# PROC054D_AWR_Pull_Resistors.net
KiCad netlist of a schematic drawn in Altium Designer
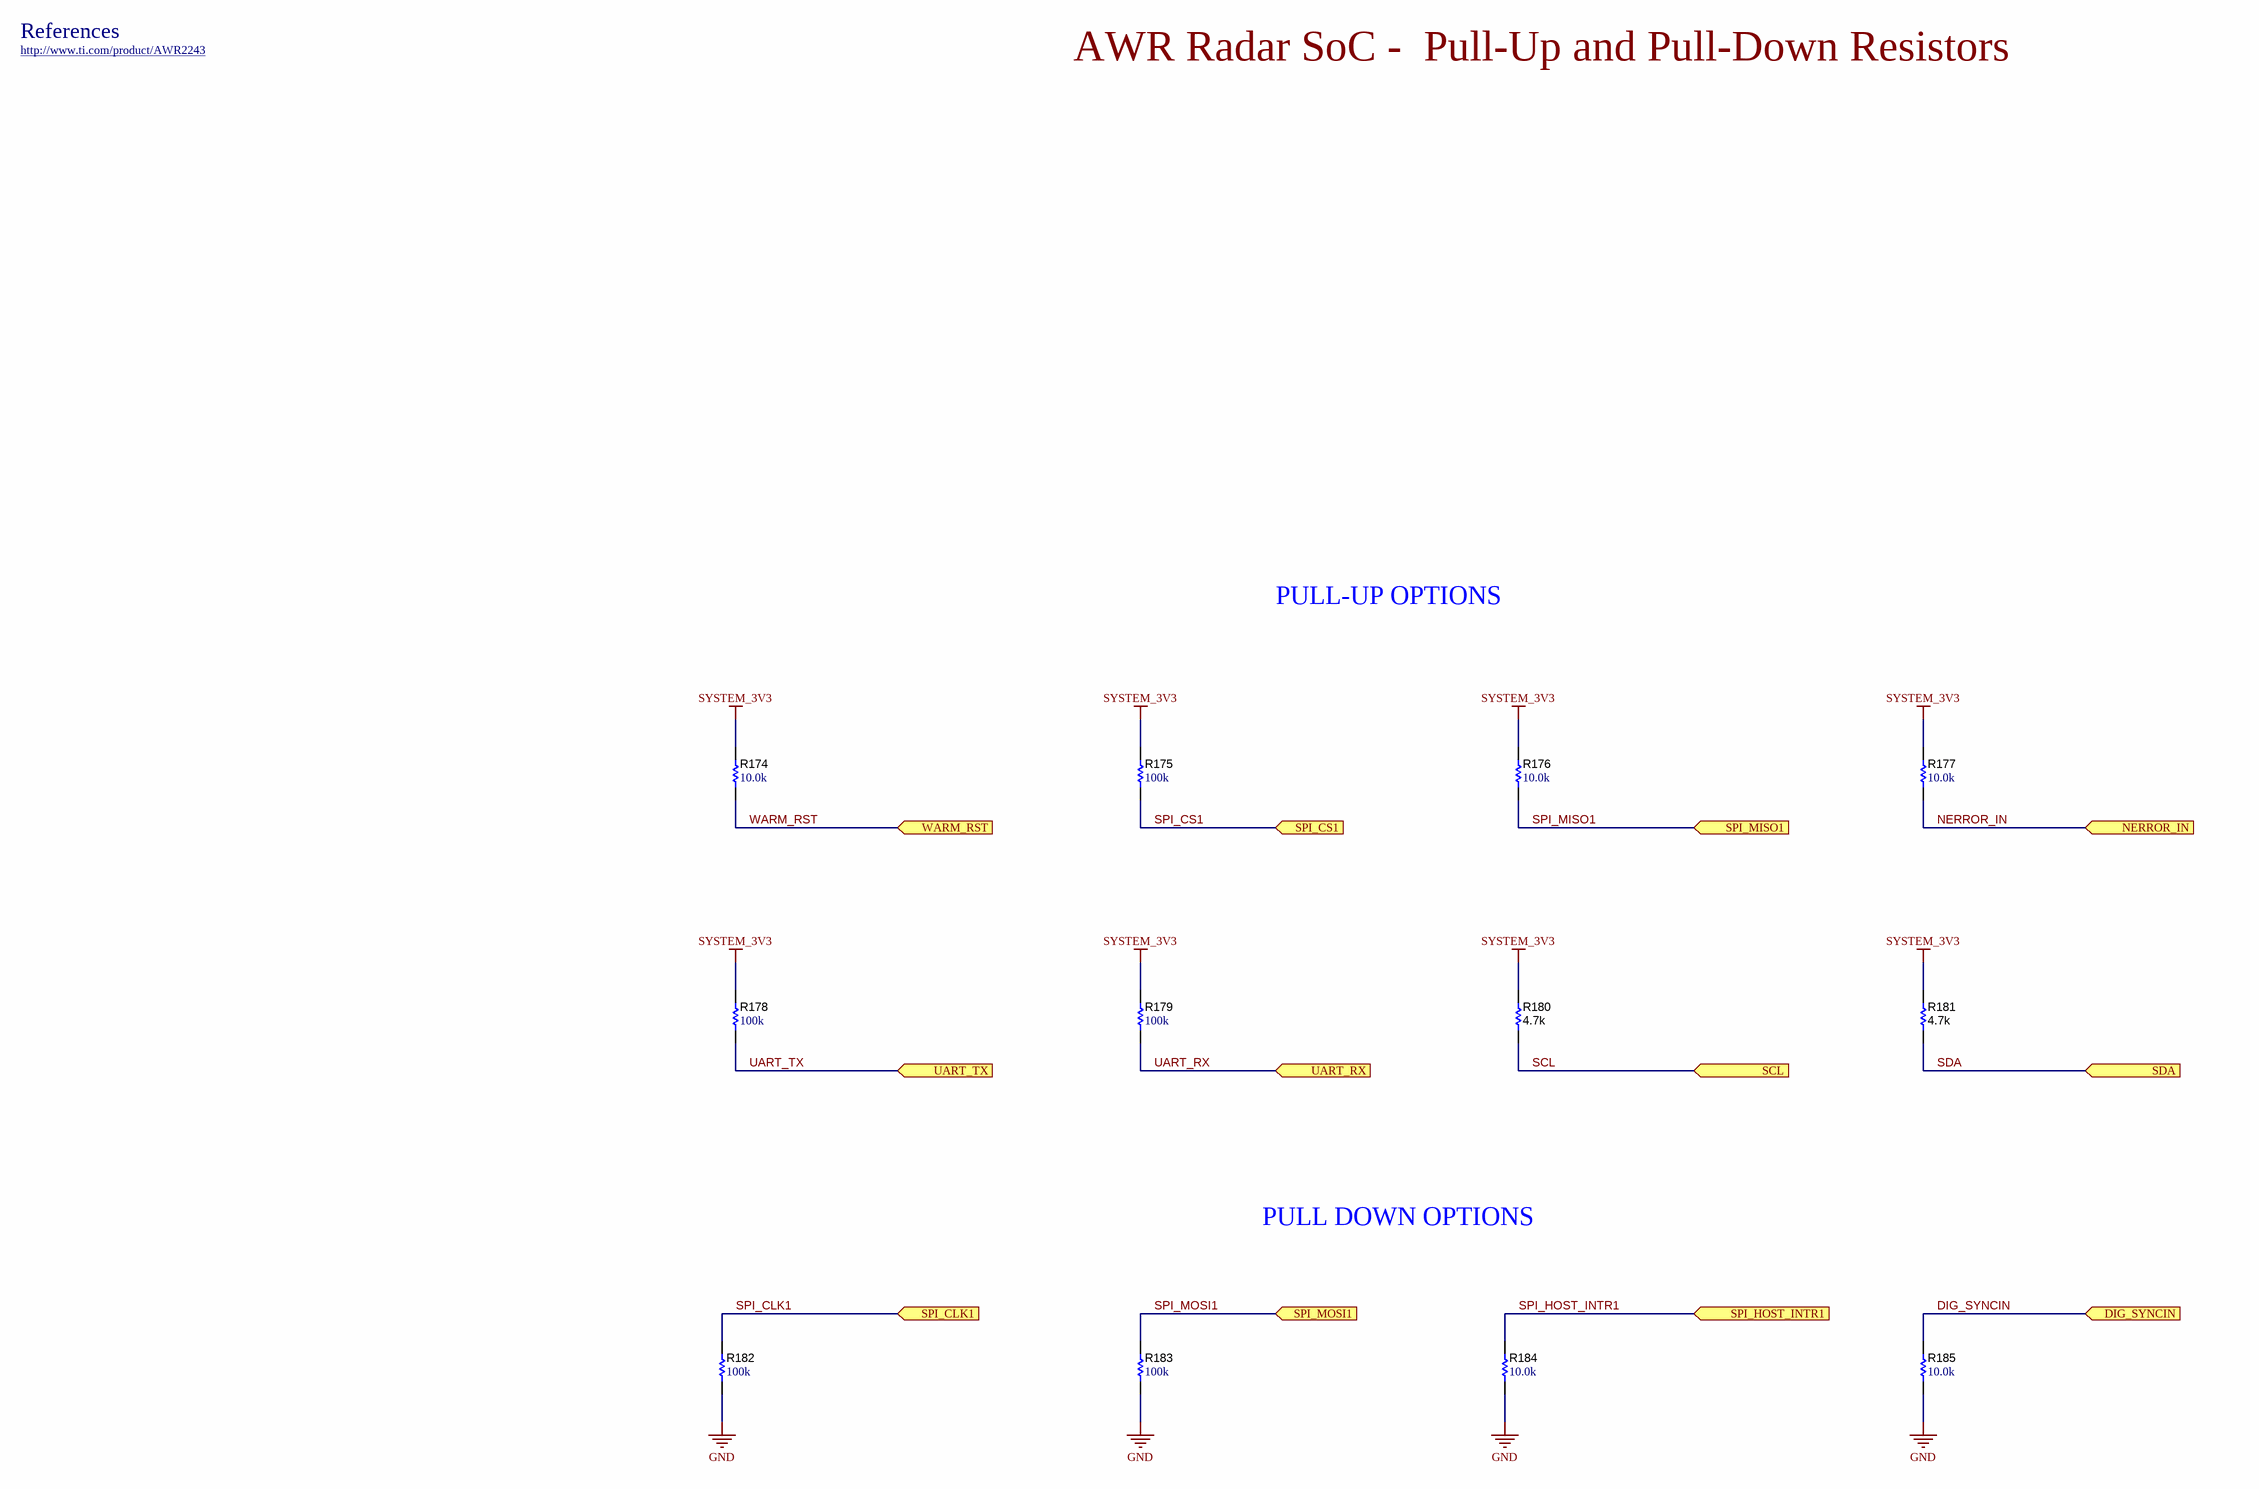
[diagram p0: PROC054D_AWR_Pull_Resistors.SchDoc]

(export (version "E")
  (design (tool "Eeschema 10.0.6"))
  (components
    (comp (ref "R174")
      (value "CRCW040210K0FKED")
      (footprint "0402")
      (description "RES, 10.0 k, 1%, 0.063 W, AEC-Q200 Grade 0, 0402")
      (fields (field (name "MANUFACTURER") "Vishay-Dale") (field (name "VALUEDISPLAYED") "10.0k"))
      (libsource (lib "Altium Vault - TI") (part "Resistor"))
    )
    (comp (ref "R175")
      (value "CRCW0402100KFKED")
      (footprint "0402")
      (description "RES, 100 k, 1%, 0.063 W, AEC-Q200 Grade 0, 0402")
      (fields (field (name "MANUFACTURER") "Vishay-Dale") (field (name "VALUEDISPLAYED") "100k"))
      (libsource (lib "Altium Vault - TI") (part "Resistor"))
    )
    (comp (ref "R176")
      (value "CRCW040210K0FKED")
      (footprint "0402")
      (description "RES, 10.0 k, 1%, 0.063 W, AEC-Q200 Grade 0, 0402")
      (fields (field (name "MANUFACTURER") "Vishay-Dale") (field (name "VALUEDISPLAYED") "10.0k"))
      (libsource (lib "Altium Vault - TI") (part "Resistor"))
    )
    (comp (ref "R177")
      (value "CRCW040210K0FKED")
      (footprint "0402S")
      (description "RES, 10.0 k, 1%, 0.063 W, AEC-Q200 Grade 0, 0402")
      (fields (field (name "MANUFACTURER") "Vishay-Dale") (field (name "VALUEDISPLAYED") "10.0k"))
      (libsource (lib "Altium Vault - TI") (part "Resistor"))
    )
    (comp (ref "R178")
      (value "CRCW0402100KFKED")
      (footprint "0402")
      (description "RES, 100 k, 1%, 0.063 W, AEC-Q200 Grade 0, 0402")
      (fields (field (name "MANUFACTURER") "Vishay-Dale") (field (name "VALUEDISPLAYED") "100k"))
      (libsource (lib "Altium Vault - TI") (part "Resistor"))
    )
    (comp (ref "R179")
      (value "CRCW0402100KFKED")
      (footprint "0402")
      (description "RES, 100 k, 1%, 0.063 W, AEC-Q200 Grade 0, 0402")
      (fields (field (name "MANUFACTURER") "Vishay-Dale") (field (name "VALUEDISPLAYED") "100k"))
      (libsource (lib "Altium Vault - TI") (part "Resistor"))
    )
    (comp (ref "R180")
      (value "CRCW04024K70JNED")
      (footprint "0402S")
      (description "RES, 4.7 k, 5%, 0.063 W, AEC-Q200 Grade 0, 0402")
      (fields (field (name "MANUFACTURER") "Vishay-Dale") (field (name "VALUEDISPLAYED") "4.7k"))
      (libsource (lib "Altium Vault - TI") (part "Resistor"))
    )
    (comp (ref "R181")
      (value "CRCW04024K70JNED")
      (footprint "0402S")
      (description "RES, 4.7 k, 5%, 0.063 W, AEC-Q200 Grade 0, 0402")
      (fields (field (name "MANUFACTURER") "Vishay-Dale") (field (name "VALUEDISPLAYED") "4.7k"))
      (libsource (lib "Altium Vault - TI") (part "Resistor"))
    )
    (comp (ref "R182")
      (value "CRCW0402100KFKED")
      (footprint "0402")
      (description "RES, 100 k, 1%, 0.063 W, AEC-Q200 Grade 0, 0402")
      (fields (field (name "MANUFACTURER") "Vishay-Dale") (field (name "VALUEDISPLAYED") "100k"))
      (libsource (lib "Altium Vault - TI") (part "Resistor"))
    )
    (comp (ref "R183")
      (value "CRCW0402100KFKED")
      (footprint "0402")
      (description "RES, 100 k, 1%, 0.063 W, AEC-Q200 Grade 0, 0402")
      (fields (field (name "MANUFACTURER") "Vishay-Dale") (field (name "VALUEDISPLAYED") "100k"))
      (libsource (lib "Altium Vault - TI") (part "Resistor"))
    )
    (comp (ref "R184")
      (value "CRCW040210K0FKED")
      (footprint "0402")
      (description "RES, 10.0 k, 1%, 0.063 W, AEC-Q200 Grade 0, 0402")
      (fields (field (name "MANUFACTURER") "Vishay-Dale") (field (name "VALUEDISPLAYED") "10.0k"))
      (libsource (lib "Altium Vault - TI") (part "Resistor"))
    )
    (comp (ref "R185")
      (value "CRCW040210K0FKED")
      (footprint "0402S")
      (description "RES, 10.0 k, 1%, 0.063 W, AEC-Q200 Grade 0, 0402")
      (fields (field (name "MANUFACTURER") "Vishay-Dale") (field (name "VALUEDISPLAYED") "10.0k"))
      (libsource (lib "Altium Vault - TI") (part "Resistor"))
    )
  )
  (nets
    (net (code "1") (name "/DIG_SYNCIN") (class "Default")
      (node (ref "R185") (pin "2") (pinfunction "2_2") (pintype "passive"))
    )
    (net (code "2") (name "/NERROR_IN") (class "Default")
      (node (ref "R177") (pin "1") (pinfunction "1_1") (pintype "passive"))
    )
    (net (code "3") (name "/SCL") (class "Default")
      (node (ref "R180") (pin "1") (pinfunction "1_1") (pintype "passive"))
    )
    (net (code "4") (name "/SDA") (class "Default")
      (node (ref "R181") (pin "1") (pinfunction "1_1") (pintype "passive"))
    )
    (net (code "5") (name "/SPI_CLK1") (class "Default")
      (node (ref "R182") (pin "2") (pinfunction "2_2") (pintype "passive"))
    )
    (net (code "6") (name "/SPI_CS1") (class "Default")
      (node (ref "R175") (pin "1") (pinfunction "1_1") (pintype "passive"))
    )
    (net (code "7") (name "/SPI_HOST_INTR1") (class "Default")
      (node (ref "R184") (pin "2") (pinfunction "2_2") (pintype "passive"))
    )
    (net (code "8") (name "/SPI_MISO1") (class "Default")
      (node (ref "R176") (pin "1") (pinfunction "1_1") (pintype "passive"))
    )
    (net (code "9") (name "/SPI_MOSI1") (class "Default")
      (node (ref "R183") (pin "2") (pinfunction "2_2") (pintype "passive"))
    )
    (net (code "10") (name "/UART_RX") (class "Default")
      (node (ref "R179") (pin "1") (pinfunction "1_1") (pintype "passive"))
    )
    (net (code "11") (name "/UART_TX") (class "Default")
      (node (ref "R178") (pin "1") (pinfunction "1_1") (pintype "passive"))
    )
    (net (code "12") (name "/WARM_RST") (class "Default")
      (node (ref "R174") (pin "1") (pinfunction "1_1") (pintype "passive"))
    )
    (net (code "13") (name "GND") (class "Default")
      (node (ref "R182") (pin "1") (pinfunction "1_1") (pintype "passive"))
      (node (ref "R183") (pin "1") (pinfunction "1_1") (pintype "passive"))
      (node (ref "R184") (pin "1") (pinfunction "1_1") (pintype "passive"))
      (node (ref "R185") (pin "1") (pinfunction "1_1") (pintype "passive"))
    )
    (net (code "14") (name "SYSTEM_3V3") (class "Default")
      (node (ref "R174") (pin "2") (pinfunction "2_2") (pintype "passive"))
      (node (ref "R175") (pin "2") (pinfunction "2_2") (pintype "passive"))
      (node (ref "R176") (pin "2") (pinfunction "2_2") (pintype "passive"))
      (node (ref "R177") (pin "2") (pinfunction "2_2") (pintype "passive"))
      (node (ref "R178") (pin "2") (pinfunction "2_2") (pintype "passive"))
      (node (ref "R179") (pin "2") (pinfunction "2_2") (pintype "passive"))
      (node (ref "R180") (pin "2") (pinfunction "2_2") (pintype "passive"))
      (node (ref "R181") (pin "2") (pinfunction "2_2") (pintype "passive"))
    )
  )
)
